# CPU.net
KiCad netlist of a schematic drawn in EAGLE
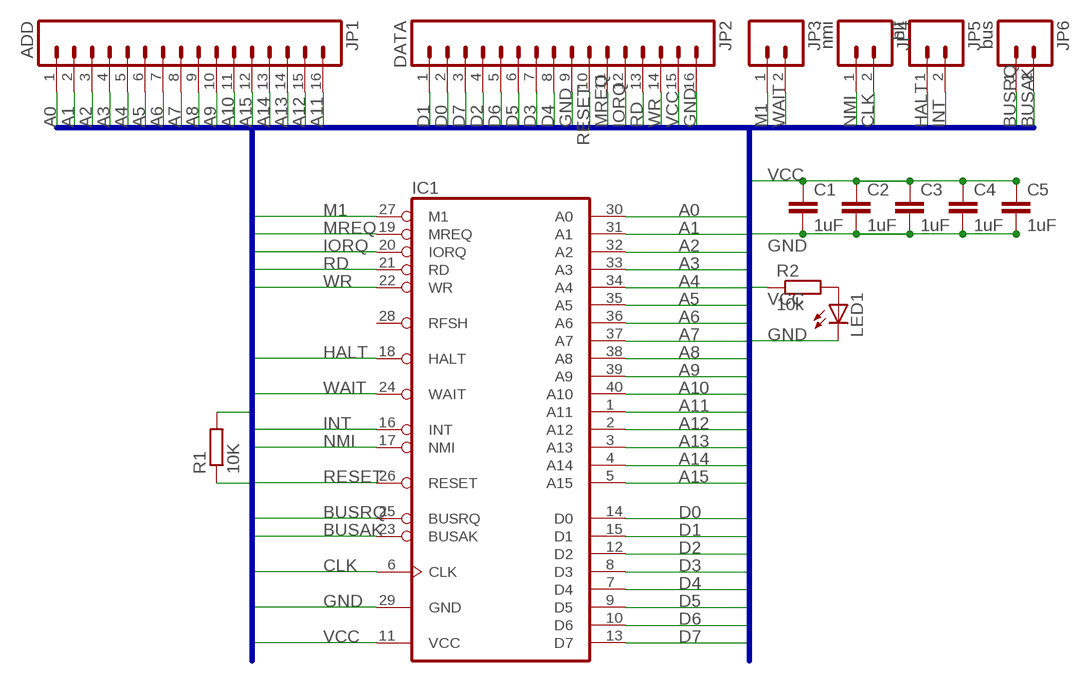
[diagram p0: schematic, sheet 1]

(export (version "E")
  (design (tool "Eeschema 10.0.6"))
  (components
    (comp (ref "C1")
      (value "1uF")
      (footprint "eagle-import:C0805")
      (libsource (lib "eagle-import") (part "C-EUC0805"))
    )
    (comp (ref "C2")
      (value "1uF")
      (footprint "eagle-import:C0805")
      (libsource (lib "eagle-import") (part "C-EUC0805"))
    )
    (comp (ref "C3")
      (value "1uF")
      (footprint "eagle-import:C0805")
      (libsource (lib "eagle-import") (part "C-EUC0805"))
    )
    (comp (ref "C4")
      (value "1uF")
      (footprint "eagle-import:C0805")
      (libsource (lib "eagle-import") (part "C-EUC0805"))
    )
    (comp (ref "C5")
      (value "1uF")
      (footprint "eagle-import:C0805")
      (libsource (lib "eagle-import") (part "C-EUC0805"))
    )
    (comp (ref "IC1")
      (value "Z80CPU")
      (footprint "eagle-import:DIL40")
      (libsource (lib "eagle-import") (part "Z80CPU"))
    )
    (comp (ref "JP1")
      (value "ADD")
      (footprint "eagle-import:1X16")
      (libsource (lib "eagle-import") (part "M16PTH"))
    )
    (comp (ref "JP2")
      (value "DATA")
      (footprint "eagle-import:1X16")
      (libsource (lib "eagle-import") (part "M16PTH"))
    )
    (comp (ref "JP3")
      (value "M02PTH")
      (footprint "eagle-import:1X02")
      (libsource (lib "eagle-import") (part "M02PTH"))
    )
    (comp (ref "JP4")
      (value "nmi")
      (footprint "eagle-import:1X02")
      (libsource (lib "eagle-import") (part "M02PTH"))
    )
    (comp (ref "JP5")
      (value "hlt")
      (footprint "eagle-import:1X02")
      (libsource (lib "eagle-import") (part "M02PTH"))
    )
    (comp (ref "JP6")
      (value "bus")
      (footprint "eagle-import:1X02")
      (libsource (lib "eagle-import") (part "M02PTH"))
    )
    (comp (ref "LED1")
      (value "LEDCHIP-LED0805")
      (footprint "eagle-import:CHIP-LED0805")
      (libsource (lib "eagle-import") (part "LEDCHIP-LED0805"))
    )
    (comp (ref "R1")
      (value "10K")
      (footprint "eagle-import:M0805")
      (libsource (lib "eagle-import") (part "R-EU_M0805"))
    )
    (comp (ref "R2")
      (value "10k")
      (footprint "eagle-import:M0805")
      (libsource (lib "eagle-import") (part "R-EU_M0805"))
    )
  )
  (nets
    (net (code "1") (name "/A0") (class "Default")
      (node (ref "IC1") (pin "30") (pinfunction "A0_30") (pintype "output"))
      (node (ref "JP1") (pin "1") (pinfunction "1_1") (pintype "passive"))
    )
    (net (code "2") (name "/A1") (class "Default")
      (node (ref "IC1") (pin "31") (pinfunction "A1_31") (pintype "output"))
      (node (ref "JP1") (pin "2") (pinfunction "2_2") (pintype "passive"))
    )
    (net (code "3") (name "/A2") (class "Default")
      (node (ref "IC1") (pin "32") (pinfunction "A2_32") (pintype "output"))
      (node (ref "JP1") (pin "3") (pinfunction "3_3") (pintype "passive"))
    )
    (net (code "4") (name "/A3") (class "Default")
      (node (ref "IC1") (pin "33") (pinfunction "A3_33") (pintype "output"))
      (node (ref "JP1") (pin "4") (pinfunction "4_4") (pintype "passive"))
    )
    (net (code "5") (name "/A4") (class "Default")
      (node (ref "IC1") (pin "34") (pinfunction "A4_34") (pintype "output"))
      (node (ref "JP1") (pin "5") (pinfunction "5_5") (pintype "passive"))
    )
    (net (code "6") (name "/A5") (class "Default")
      (node (ref "IC1") (pin "35") (pinfunction "A5_35") (pintype "output"))
      (node (ref "JP1") (pin "6") (pinfunction "6_6") (pintype "passive"))
    )
    (net (code "7") (name "/A6") (class "Default")
      (node (ref "IC1") (pin "36") (pinfunction "A6_36") (pintype "output"))
      (node (ref "JP1") (pin "7") (pinfunction "7_7") (pintype "passive"))
    )
    (net (code "8") (name "/A7") (class "Default")
      (node (ref "IC1") (pin "37") (pinfunction "A7_37") (pintype "output"))
      (node (ref "JP1") (pin "8") (pinfunction "8_8") (pintype "passive"))
    )
    (net (code "9") (name "/A8") (class "Default")
      (node (ref "IC1") (pin "38") (pinfunction "A8_38") (pintype "output"))
      (node (ref "JP1") (pin "9") (pinfunction "9_9") (pintype "passive"))
    )
    (net (code "10") (name "/A9") (class "Default")
      (node (ref "IC1") (pin "39") (pinfunction "A9_39") (pintype "output"))
      (node (ref "JP1") (pin "10") (pinfunction "10_10") (pintype "passive"))
    )
    (net (code "11") (name "/A10") (class "Default")
      (node (ref "IC1") (pin "40") (pinfunction "A10_40") (pintype "output"))
      (node (ref "JP1") (pin "11") (pinfunction "11_11") (pintype "passive"))
    )
    (net (code "12") (name "/A11") (class "Default")
      (node (ref "IC1") (pin "1") (pinfunction "A11_1") (pintype "output"))
      (node (ref "JP1") (pin "16") (pinfunction "16_16") (pintype "passive"))
    )
    (net (code "13") (name "/A12") (class "Default")
      (node (ref "IC1") (pin "2") (pinfunction "A12_2") (pintype "output"))
      (node (ref "JP1") (pin "15") (pinfunction "15_15") (pintype "passive"))
    )
    (net (code "14") (name "/A13") (class "Default")
      (node (ref "IC1") (pin "3") (pinfunction "A13_3") (pintype "output"))
      (node (ref "JP1") (pin "14") (pinfunction "14_14") (pintype "passive"))
    )
    (net (code "15") (name "/A14") (class "Default")
      (node (ref "IC1") (pin "4") (pinfunction "A14_4") (pintype "output"))
      (node (ref "JP1") (pin "13") (pinfunction "13_13") (pintype "passive"))
    )
    (net (code "16") (name "/A15") (class "Default")
      (node (ref "IC1") (pin "5") (pinfunction "A15_5") (pintype "output"))
      (node (ref "JP1") (pin "12") (pinfunction "12_12") (pintype "passive"))
    )
    (net (code "17") (name "/BUSAK") (class "Default")
      (node (ref "IC1") (pin "23") (pinfunction "BUSAK_23") (pintype "output"))
      (node (ref "JP6") (pin "2") (pinfunction "2_2") (pintype "passive"))
    )
    (net (code "18") (name "/BUSRQ") (class "Default")
      (node (ref "IC1") (pin "25") (pinfunction "BUSRQ_25") (pintype "input"))
      (node (ref "JP6") (pin "1") (pinfunction "1_1") (pintype "passive"))
    )
    (net (code "19") (name "/CLK") (class "Default")
      (node (ref "IC1") (pin "6") (pinfunction "CLK_6") (pintype "input"))
      (node (ref "JP4") (pin "2") (pinfunction "2_2") (pintype "passive"))
    )
    (net (code "20") (name "/D0") (class "Default")
      (node (ref "IC1") (pin "14") (pinfunction "D0_14") (pintype "bidirectional"))
      (node (ref "JP2") (pin "2") (pinfunction "2_2") (pintype "passive"))
    )
    (net (code "21") (name "/D1") (class "Default")
      (node (ref "IC1") (pin "15") (pinfunction "D1_15") (pintype "bidirectional"))
      (node (ref "JP2") (pin "1") (pinfunction "1_1") (pintype "passive"))
    )
    (net (code "22") (name "/D2") (class "Default")
      (node (ref "IC1") (pin "12") (pinfunction "D2_12") (pintype "bidirectional"))
      (node (ref "JP2") (pin "4") (pinfunction "4_4") (pintype "passive"))
    )
    (net (code "23") (name "/D3") (class "Default")
      (node (ref "IC1") (pin "8") (pinfunction "D3_8") (pintype "bidirectional"))
      (node (ref "JP2") (pin "7") (pinfunction "7_7") (pintype "passive"))
    )
    (net (code "24") (name "/D4") (class "Default")
      (node (ref "IC1") (pin "7") (pinfunction "D4_7") (pintype "bidirectional"))
      (node (ref "JP2") (pin "8") (pinfunction "8_8") (pintype "passive"))
    )
    (net (code "25") (name "/D5") (class "Default")
      (node (ref "IC1") (pin "9") (pinfunction "D5_9") (pintype "bidirectional"))
      (node (ref "JP2") (pin "6") (pinfunction "6_6") (pintype "passive"))
    )
    (net (code "26") (name "/D6") (class "Default")
      (node (ref "IC1") (pin "10") (pinfunction "D6_10") (pintype "bidirectional"))
      (node (ref "JP2") (pin "5") (pinfunction "5_5") (pintype "passive"))
    )
    (net (code "27") (name "/D7") (class "Default")
      (node (ref "IC1") (pin "13") (pinfunction "D7_13") (pintype "bidirectional"))
      (node (ref "JP2") (pin "3") (pinfunction "3_3") (pintype "passive"))
    )
    (net (code "28") (name "/GND") (class "Default")
      (node (ref "C1") (pin "2") (pinfunction "2_2") (pintype "passive"))
      (node (ref "C2") (pin "2") (pinfunction "2_2") (pintype "passive"))
      (node (ref "C3") (pin "2") (pinfunction "2_2") (pintype "passive"))
      (node (ref "C4") (pin "2") (pinfunction "2_2") (pintype "passive"))
      (node (ref "C5") (pin "2") (pinfunction "2_2") (pintype "passive"))
      (node (ref "IC1") (pin "29") (pinfunction "GND_29") (pintype "power_in"))
      (node (ref "JP2") (pin "16") (pinfunction "16_16") (pintype "passive"))
      (node (ref "JP2") (pin "9") (pinfunction "9_9") (pintype "passive"))
      (node (ref "LED1") (pin "C") (pinfunction "C_C") (pintype "passive"))
    )
    (net (code "29") (name "/HALT") (class "Default")
      (node (ref "IC1") (pin "18") (pinfunction "HALT_18") (pintype "output"))
      (node (ref "JP5") (pin "1") (pinfunction "1_1") (pintype "passive"))
    )
    (net (code "30") (name "/INT") (class "Default")
      (node (ref "IC1") (pin "16") (pinfunction "INT_16") (pintype "input"))
      (node (ref "JP5") (pin "2") (pinfunction "2_2") (pintype "passive"))
    )
    (net (code "31") (name "/IORQ") (class "Default")
      (node (ref "IC1") (pin "20") (pinfunction "IORQ_20") (pintype "output"))
      (node (ref "JP2") (pin "12") (pinfunction "12_12") (pintype "passive"))
    )
    (net (code "32") (name "/M1") (class "Default")
      (node (ref "IC1") (pin "27") (pinfunction "M1_27") (pintype "output"))
      (node (ref "JP3") (pin "1") (pinfunction "1_1") (pintype "passive"))
    )
    (net (code "33") (name "/MREQ") (class "Default")
      (node (ref "IC1") (pin "19") (pinfunction "MREQ_19") (pintype "output"))
      (node (ref "JP2") (pin "11") (pinfunction "11_11") (pintype "passive"))
    )
    (net (code "34") (name "/NMI") (class "Default")
      (node (ref "IC1") (pin "17") (pinfunction "NMI_17") (pintype "input"))
      (node (ref "JP4") (pin "1") (pinfunction "1_1") (pintype "passive"))
    )
    (net (code "35") (name "/RD") (class "Default")
      (node (ref "IC1") (pin "21") (pinfunction "RD_21") (pintype "output"))
      (node (ref "JP2") (pin "13") (pinfunction "13_13") (pintype "passive"))
    )
    (net (code "36") (name "/RESET") (class "Default")
      (node (ref "IC1") (pin "26") (pinfunction "RESET_26") (pintype "input"))
      (node (ref "JP2") (pin "10") (pinfunction "10_10") (pintype "passive"))
      (node (ref "R1") (pin "1") (pinfunction "1_1") (pintype "passive"))
    )
    (net (code "37") (name "/VCC") (class "Default")
      (node (ref "C1") (pin "1") (pinfunction "1_1") (pintype "passive"))
      (node (ref "C2") (pin "1") (pinfunction "1_1") (pintype "passive"))
      (node (ref "C3") (pin "1") (pinfunction "1_1") (pintype "passive"))
      (node (ref "C4") (pin "1") (pinfunction "1_1") (pintype "passive"))
      (node (ref "C5") (pin "1") (pinfunction "1_1") (pintype "passive"))
      (node (ref "IC1") (pin "11") (pinfunction "VCC_11") (pintype "power_in"))
      (node (ref "JP2") (pin "15") (pinfunction "15_15") (pintype "passive"))
      (node (ref "R1") (pin "2") (pinfunction "2_2") (pintype "passive"))
      (node (ref "R2") (pin "1") (pinfunction "1_1") (pintype "passive"))
    )
    (net (code "38") (name "/WAIT") (class "Default")
      (node (ref "IC1") (pin "24") (pinfunction "WAIT_24") (pintype "input"))
      (node (ref "JP3") (pin "2") (pinfunction "2_2") (pintype "passive"))
    )
    (net (code "39") (name "/WR") (class "Default")
      (node (ref "IC1") (pin "22") (pinfunction "WR_22") (pintype "output"))
      (node (ref "JP2") (pin "14") (pinfunction "14_14") (pintype "passive"))
    )
    (net (code "40") (name "Net-(LED1-PadA)") (class "Default")
      (node (ref "LED1") (pin "A") (pinfunction "A_A") (pintype "passive"))
      (node (ref "R2") (pin "2") (pinfunction "2_2") (pintype "passive"))
    )
    (net (code "41") (name "unconnected-(IC1-RFSH-Pad28)") (class "Default")
      (node (ref "IC1") (pin "28") (pinfunction "RFSH_28") (pintype "output"))
    )
  )
)
